# myf14.net
KiCad netlist of a schematic drawn in EAGLE
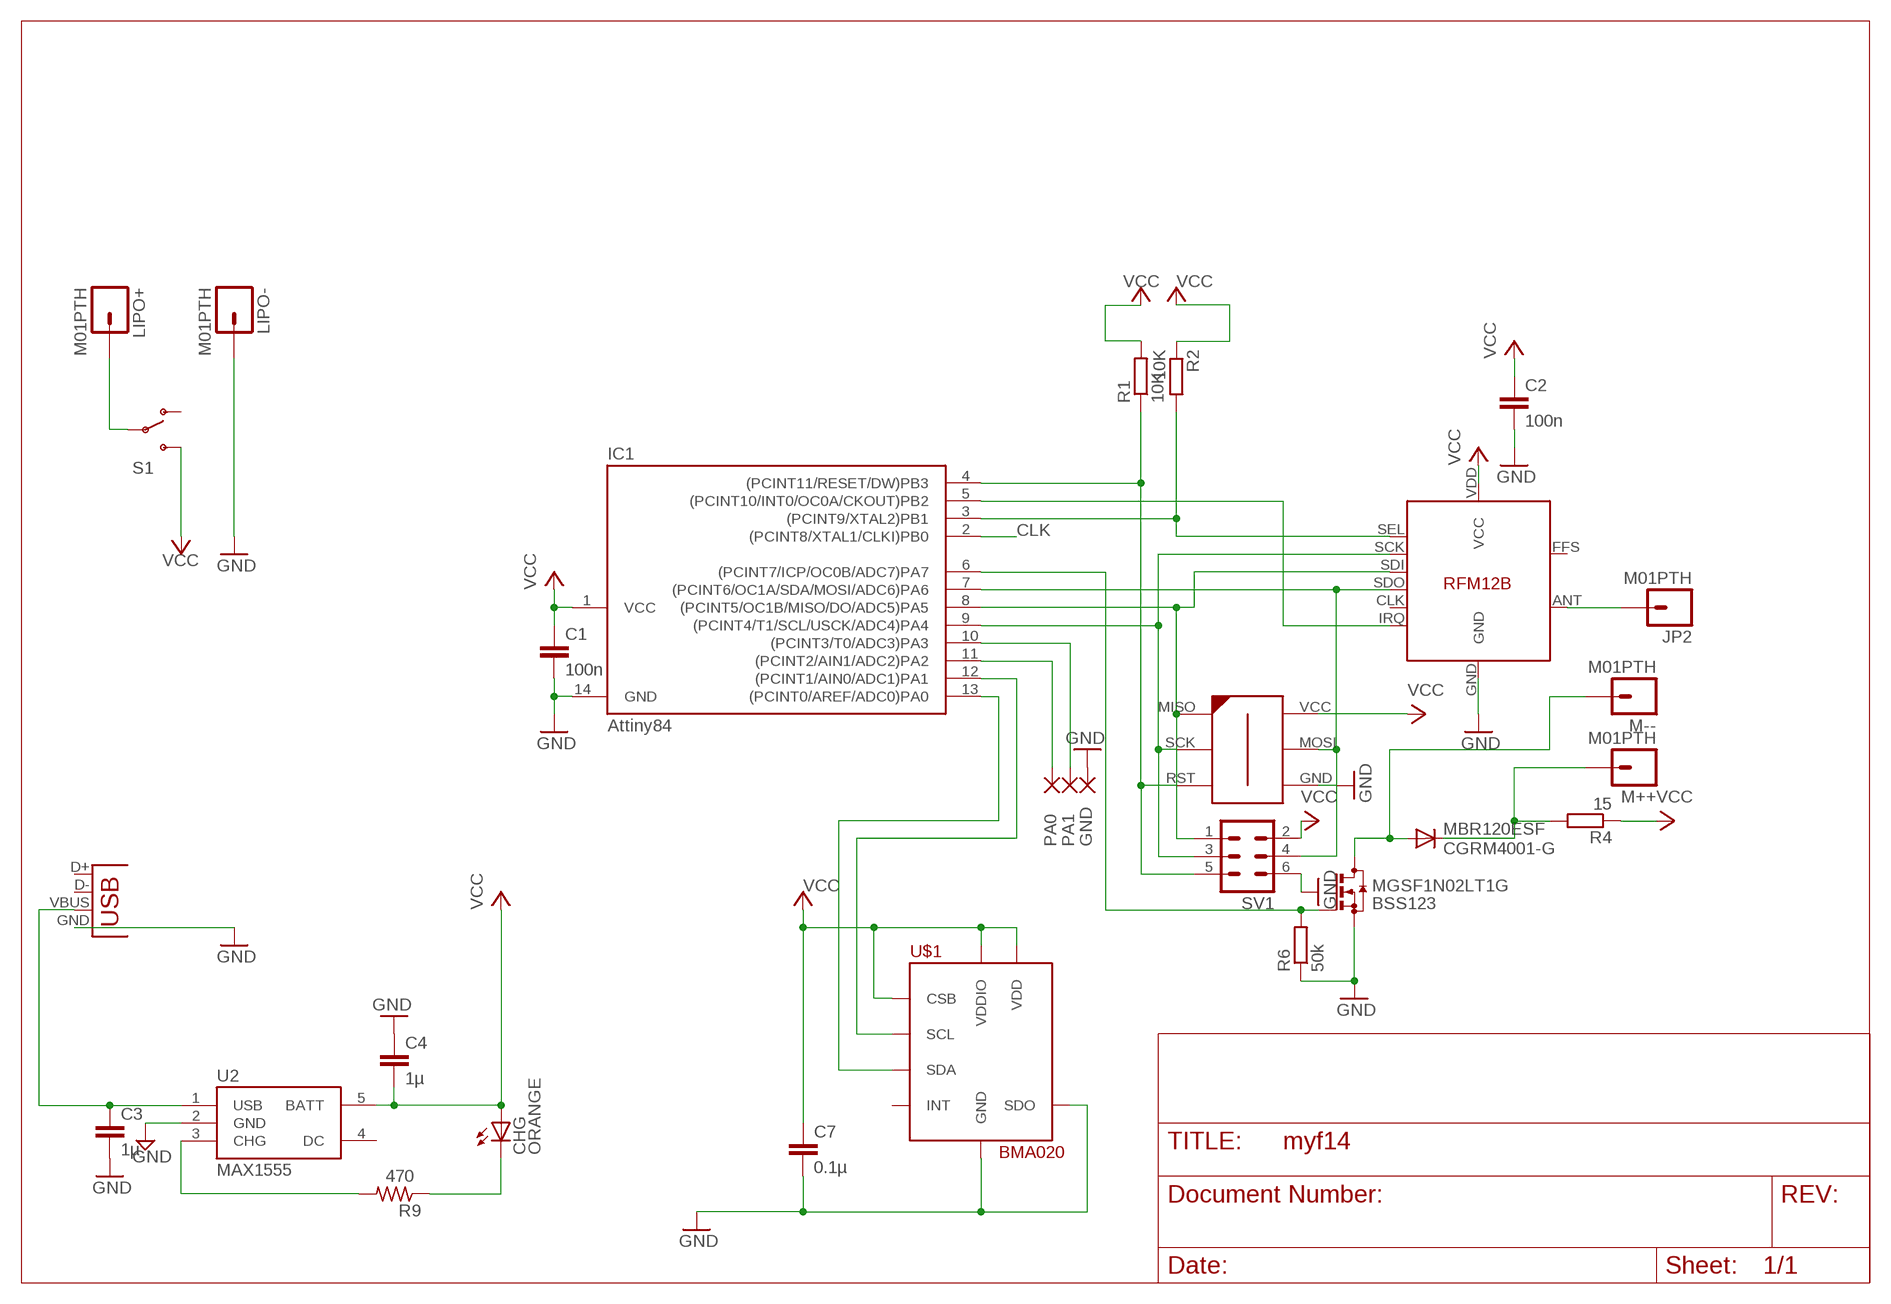
[diagram p0: schematic, sheet 1]

(export (version "E")
  (design (tool "Eeschema 10.0.6"))
  (components
    (comp (ref "C1")
      (value "100n")
      (footprint "eagle-import:C0603K")
      (libsource (lib "eagle-import") (part "C-EUC0603K"))
    )
    (comp (ref "C2")
      (value "100n")
      (footprint "eagle-import:C0603K")
      (libsource (lib "eagle-import") (part "C-EUC0603K"))
    )
    (comp (ref "C3")
      (value "1µ")
      (footprint "eagle-import:0603-CAP")
      (libsource (lib "eagle-import") (part "CAP0603-CAP"))
    )
    (comp (ref "C4")
      (value "1µ")
      (footprint "eagle-import:0603-CAP")
      (libsource (lib "eagle-import") (part "CAP0603-CAP"))
    )
    (comp (ref "C7")
      (value "0.1µ")
      (footprint "eagle-import:0603-CAP")
      (libsource (lib "eagle-import") (part "CAP0603-CAP"))
    )
    (comp (ref "CHG")
      (value "ORANGE")
      (footprint "eagle-import:LED-0603")
      (libsource (lib "eagle-import") (part "LED0603"))
    )
    (comp (ref "GND")
      (value "SMD2")
      (footprint "eagle-import:SMD1,27-2,54")
      (libsource (lib "eagle-import") (part "SMD2"))
    )
    (comp (ref "IC1")
      (value "Attiny84")
      (footprint "eagle-import:SOIC14")
      (libsource (lib "eagle-import") (part "TINY24/44/84-SSU"))
    )
    (comp (ref "JP2")
      (value "M01PTH")
      (footprint "eagle-import:1X01")
      (libsource (lib "eagle-import") (part "M01PTH"))
    )
    (comp (ref "LIPO+")
      (value "M01PTH")
      (footprint "eagle-import:1X01")
      (libsource (lib "eagle-import") (part "M01PTH"))
    )
    (comp (ref "LIPO-")
      (value "M01PTH")
      (footprint "eagle-import:1X01")
      (libsource (lib "eagle-import") (part "M01PTH"))
    )
    (comp (ref "M++")
      (value "M01PTH")
      (footprint "eagle-import:1X01")
      (libsource (lib "eagle-import") (part "M01PTH"))
    )
    (comp (ref "M--")
      (value "M01PTH")
      (footprint "eagle-import:1X01")
      (libsource (lib "eagle-import") (part "M01PTH"))
    )
    (comp (ref "MBR120ESF")
      (value "CGRM4001-G")
      (footprint "eagle-import:SOD-123_MINI-SMA")
      (libsource (lib "eagle-import") (part "CGRM400-G1"))
    )
    (comp (ref "MGSF1N02LT1G")
      (value "BSS123")
      (footprint "eagle-import:SOT23")
      (libsource (lib "eagle-import") (part "BSS123"))
    )
    (comp (ref "PA0")
      (value "SMD2")
      (footprint "eagle-import:SMD1,27-2,54")
      (libsource (lib "eagle-import") (part "SMD2"))
    )
    (comp (ref "PA1")
      (value "SMD2")
      (footprint "eagle-import:SMD1,27-2,54")
      (libsource (lib "eagle-import") (part "SMD2"))
    )
    (comp (ref "R1")
      (value "10K")
      (footprint "eagle-import:R0603")
      (libsource (lib "eagle-import") (part "R-EU_R0603"))
    )
    (comp (ref "R2")
      (value "10K")
      (footprint "eagle-import:R0603")
      (libsource (lib "eagle-import") (part "R-EU_R0603"))
    )
    (comp (ref "R4")
      (value "15")
      (footprint "eagle-import:R0603")
      (libsource (lib "eagle-import") (part "R-EU_R0603"))
    )
    (comp (ref "R6")
      (value "50k")
      (footprint "eagle-import:R0603")
      (libsource (lib "eagle-import") (part "R-EU_R0603"))
    )
    (comp (ref "R9")
      (value "470")
      (footprint "eagle-import:R0603")
      (libsource (lib "eagle-import") (part "R-US_R0603"))
    )
    (comp (ref "RFM12B")
      (value "RFM12B")
      (footprint "eagle-import:RFM12B")
      (libsource (lib "eagle-import") (part "RFM12B"))
    )
    (comp (ref "S1")
      (value "SWITCH-SPDTSMD")
      (footprint "eagle-import:AYZ0202")
      (libsource (lib "eagle-import") (part "SWITCH-SPDTSMD"))
    )
    (comp (ref "SV1")
      (value "MA03-2S")
      (footprint "eagle-import:MA03-2-0.8")
      (libsource (lib "eagle-import") (part "MA03-2S"))
    )
    (comp (ref "U$1")
      (value "BMA020")
      (footprint "eagle-import:LBA-12")
      (libsource (lib "eagle-import") (part "BMA020"))
    )
    (comp (ref "U$2")
      (value "AVR-ISP-6-EDGE")
      (footprint "eagle-import:6PAD_ISP")
      (libsource (lib "eagle-import") (part "AVR-ISP-6-EDGE"))
    )
    (comp (ref "U2")
      (value "MAX1555")
      (footprint "eagle-import:SOT23-5")
      (libsource (lib "eagle-import") (part "MAX1555"))
    )
    (comp (ref "X1")
      (value "USB-MICROB")
      (footprint "eagle-import:USB-MICROB")
      (libsource (lib "eagle-import") (part "USB-MICROB"))
    )
  )
  (nets
    (net (code "1") (name "/CLK") (class "Default")
      (node (ref "IC1") (pin "2") (pinfunction "(PCINT8/XTAL1/CLKI)PB0_2") (pintype "bidirectional"))
    )
    (net (code "2") (name "GND") (class "Default")
      (node (ref "C1") (pin "2") (pinfunction "2_2") (pintype "passive"))
      (node (ref "C2") (pin "2") (pinfunction "2_2") (pintype "passive"))
      (node (ref "C3") (pin "2") (pinfunction "2_2") (pintype "passive"))
      (node (ref "C4") (pin "1") (pinfunction "1_1") (pintype "passive"))
      (node (ref "C7") (pin "2") (pinfunction "2_2") (pintype "passive"))
      (node (ref "GND") (pin "1") (pinfunction "P_1") (pintype "passive"))
      (node (ref "IC1") (pin "14") (pinfunction "GND_14") (pintype "power_in"))
      (node (ref "LIPO-") (pin "1") (pinfunction "1_1") (pintype "passive"))
      (node (ref "MGSF1N02LT1G") (pin "2") (pinfunction "S_2") (pintype "passive"))
      (node (ref "R6") (pin "1") (pinfunction "1_1") (pintype "passive"))
      (node (ref "RFM12B") (pin "GND") (pinfunction "GND_GND") (pintype "power_in"))
      (node (ref "SV1") (pin "6") (pinfunction "6_6") (pintype "passive"))
      (node (ref "U$1") (pin "P$3") (pinfunction "GND_P$3") (pintype "power_in"))
      (node (ref "U$1") (pin "P$7") (pinfunction "SDO_P$7") (pintype "bidirectional"))
      (node (ref "U$2") (pin "GND") (pinfunction "P$4_GND") (pintype "bidirectional"))
      (node (ref "U2") (pin "2") (pinfunction "GND_2") (pintype "bidirectional"))
      (node (ref "X1") (pin "GND") (pinfunction "GND_GND") (pintype "bidirectional"))
    )
    (net (code "3") (name "Net-(CHG-PadC)") (class "Default")
      (node (ref "CHG") (pin "C") (pinfunction "C_C") (pintype "passive"))
      (node (ref "R9") (pin "1") (pinfunction "1_1") (pintype "passive"))
    )
    (net (code "4") (name "Net-(IC1-(PCINT0{slash}AREF{slash}ADC0)PA0)") (class "Default")
      (node (ref "IC1") (pin "13") (pinfunction "(PCINT0/AREF/ADC0)PA0_13") (pintype "bidirectional"))
      (node (ref "U$1") (pin "P$8") (pinfunction "SDA_P$8") (pintype "bidirectional"))
    )
    (net (code "5") (name "Net-(IC1-(PCINT1{slash}AIN0{slash}ADC1)PA1)") (class "Default")
      (node (ref "IC1") (pin "12") (pinfunction "(PCINT1/AIN0/ADC1)PA1_12") (pintype "bidirectional"))
      (node (ref "U$1") (pin "P$6") (pinfunction "SCL_P$6") (pintype "bidirectional"))
    )
    (net (code "6") (name "Net-(IC1-(PCINT2{slash}AIN1{slash}ADC2)PA2)") (class "Default")
      (node (ref "IC1") (pin "11") (pinfunction "(PCINT2/AIN1/ADC2)PA2_11") (pintype "bidirectional"))
      (node (ref "PA0") (pin "1") (pinfunction "P_1") (pintype "passive"))
    )
    (net (code "7") (name "Net-(IC1-(PCINT3{slash}T0{slash}ADC3)PA3)") (class "Default")
      (node (ref "IC1") (pin "10") (pinfunction "(PCINT3/T0/ADC3)PA3_10") (pintype "bidirectional"))
      (node (ref "PA1") (pin "1") (pinfunction "P_1") (pintype "passive"))
    )
    (net (code "8") (name "Net-(IC1-(PCINT4{slash}T1{slash}SCL{slash}USCK{slash}ADC4)PA4)") (class "Default")
      (node (ref "IC1") (pin "9") (pinfunction "(PCINT4/T1/SCL/USCK/ADC4)PA4_9") (pintype "bidirectional"))
      (node (ref "RFM12B") (pin "SCK") (pinfunction "SCK_SCK") (pintype "input"))
      (node (ref "SV1") (pin "3") (pinfunction "3_3") (pintype "passive"))
      (node (ref "U$2") (pin "SCK") (pinfunction "P$2_SCK") (pintype "bidirectional"))
    )
    (net (code "9") (name "Net-(IC1-(PCINT5{slash}OC1B{slash}MISO{slash}DO{slash}ADC5)PA5)") (class "Default")
      (node (ref "IC1") (pin "8") (pinfunction "(PCINT5/OC1B/MISO/DO/ADC5)PA5_8") (pintype "bidirectional"))
      (node (ref "RFM12B") (pin "SDI") (pinfunction "SDI_SDI") (pintype "input"))
      (node (ref "SV1") (pin "1") (pinfunction "1_1") (pintype "passive"))
      (node (ref "U$2") (pin "MISO") (pinfunction "P$1_MISO") (pintype "bidirectional"))
    )
    (net (code "10") (name "Net-(IC1-(PCINT6{slash}OC1A{slash}SDA{slash}MOSI{slash}ADC6)PA6)") (class "Default")
      (node (ref "IC1") (pin "7") (pinfunction "(PCINT6/OC1A/SDA/MOSI/ADC6)PA6_7") (pintype "bidirectional"))
      (node (ref "RFM12B") (pin "SDO") (pinfunction "SDO_SDO") (pintype "output"))
      (node (ref "SV1") (pin "4") (pinfunction "4_4") (pintype "passive"))
      (node (ref "U$2") (pin "MOSI") (pinfunction "P$5_MOSI") (pintype "bidirectional"))
    )
    (net (code "11") (name "Net-(IC1-(PCINT7{slash}ICP{slash}OC0B{slash}ADC7)PA7)") (class "Default")
      (node (ref "IC1") (pin "6") (pinfunction "(PCINT7/ICP/OC0B/ADC7)PA7_6") (pintype "bidirectional"))
      (node (ref "MGSF1N02LT1G") (pin "1") (pinfunction "G_1") (pintype "passive"))
      (node (ref "R6") (pin "2") (pinfunction "2_2") (pintype "passive"))
    )
    (net (code "12") (name "Net-(IC1-(PCINT9{slash}XTAL2)PB1)") (class "Default")
      (node (ref "IC1") (pin "3") (pinfunction "(PCINT9/XTAL2)PB1_3") (pintype "bidirectional"))
      (node (ref "R2") (pin "2") (pinfunction "2_2") (pintype "passive"))
      (node (ref "RFM12B") (pin "SEL") (pinfunction "SEL_SEL") (pintype "input"))
    )
    (net (code "13") (name "Net-(IC1-(PCINT10{slash}INT0{slash}OC0A{slash}CKOUT)PB2)") (class "Default")
      (node (ref "IC1") (pin "5") (pinfunction "(PCINT10/INT0/OC0A/CKOUT)PB2_5") (pintype "bidirectional"))
      (node (ref "RFM12B") (pin "IRQ") (pinfunction "IRQ_IRQ") (pintype "open_collector"))
    )
    (net (code "14") (name "Net-(IC1-(PCINT11{slash}RESET{slash}DW)PB3)") (class "Default")
      (node (ref "IC1") (pin "4") (pinfunction "(PCINT11/RESET/DW)PB3_4") (pintype "bidirectional"))
      (node (ref "R1") (pin "1") (pinfunction "1_1") (pintype "passive"))
      (node (ref "SV1") (pin "5") (pinfunction "5_5") (pintype "passive"))
      (node (ref "U$2") (pin "RST") (pinfunction "P$3_RST") (pintype "bidirectional"))
    )
    (net (code "15") (name "Net-(JP2-Pad1)") (class "Default")
      (node (ref "JP2") (pin "1") (pinfunction "1_1") (pintype "passive"))
      (node (ref "RFM12B") (pin "ANT") (pinfunction "ANT_ANT") (pintype "passive"))
    )
    (net (code "16") (name "Net-(M++-Pad1)") (class "Default")
      (node (ref "M++") (pin "1") (pinfunction "1_1") (pintype "passive"))
      (node (ref "MBR120ESF") (pin "C") (pinfunction "C_C") (pintype "passive"))
      (node (ref "R4") (pin "2") (pinfunction "2_2") (pintype "passive"))
    )
    (net (code "17") (name "Net-(MGSF1N02LT1G-D)") (class "Default")
      (node (ref "M--") (pin "1") (pinfunction "1_1") (pintype "passive"))
      (node (ref "MBR120ESF") (pin "A") (pinfunction "A_A") (pintype "passive"))
      (node (ref "MGSF1N02LT1G") (pin "3") (pinfunction "D_3") (pintype "passive"))
    )
    (net (code "18") (name "Net-(S1-P)") (class "Default")
      (node (ref "LIPO+") (pin "1") (pinfunction "1_1") (pintype "passive"))
      (node (ref "S1") (pin "2") (pinfunction "P_2") (pintype "passive"))
    )
    (net (code "19") (name "Net-(U2-CHG)") (class "Default")
      (node (ref "R9") (pin "2") (pinfunction "2_2") (pintype "passive"))
      (node (ref "U2") (pin "3") (pinfunction "CHG_3") (pintype "bidirectional"))
    )
    (net (code "20") (name "Net-(U2-USB)") (class "Default")
      (node (ref "C3") (pin "1") (pinfunction "1_1") (pintype "passive"))
      (node (ref "U2") (pin "1") (pinfunction "USB_1") (pintype "bidirectional"))
      (node (ref "X1") (pin "VBUS") (pinfunction "VBUS_VBUS") (pintype "bidirectional"))
    )
    (net (code "21") (name "VCC") (class "Default")
      (node (ref "C1") (pin "1") (pinfunction "1_1") (pintype "passive"))
      (node (ref "C2") (pin "1") (pinfunction "1_1") (pintype "passive"))
      (node (ref "C4") (pin "2") (pinfunction "2_2") (pintype "passive"))
      (node (ref "C7") (pin "1") (pinfunction "1_1") (pintype "passive"))
      (node (ref "CHG") (pin "A") (pinfunction "A_A") (pintype "passive"))
      (node (ref "IC1") (pin "1") (pinfunction "VCC_1") (pintype "power_in"))
      (node (ref "R1") (pin "2") (pinfunction "2_2") (pintype "passive"))
      (node (ref "R2") (pin "1") (pinfunction "1_1") (pintype "passive"))
      (node (ref "R4") (pin "1") (pinfunction "1_1") (pintype "passive"))
      (node (ref "RFM12B") (pin "VDD") (pinfunction "VCC_VDD") (pintype "power_in"))
      (node (ref "S1") (pin "3") (pinfunction "S_3") (pintype "passive"))
      (node (ref "SV1") (pin "2") (pinfunction "2_2") (pintype "passive"))
      (node (ref "U$1") (pin "P$2") (pinfunction "VDD_P$2") (pintype "power_in"))
      (node (ref "U$1") (pin "P$5") (pinfunction "CSB_P$5") (pintype "bidirectional"))
      (node (ref "U$1") (pin "P$9") (pinfunction "VDDIO_P$9") (pintype "power_in"))
      (node (ref "U$2") (pin "VCC") (pinfunction "P$6_VCC") (pintype "bidirectional"))
      (node (ref "U2") (pin "5") (pinfunction "BATT_5") (pintype "bidirectional"))
    )
    (net (code "22") (name "unconnected-(RFM12B-PadCLK)") (class "Default")
      (node (ref "RFM12B") (pin "CLK") (pinfunction "CLK_CLK") (pintype "output"))
    )
    (net (code "23") (name "unconnected-(RFM12B-PadFFS)") (class "Default")
      (node (ref "RFM12B") (pin "FFS") (pinfunction "FFS_FFS") (pintype "bidirectional"))
    )
    (net (code "24") (name "unconnected-(S1-O-Pad1)") (class "Default")
      (node (ref "S1") (pin "1") (pinfunction "O_1") (pintype "passive"))
    )
    (net (code "25") (name "unconnected-(U$1-INT-PadP$4)") (class "Default")
      (node (ref "U$1") (pin "P$4") (pinfunction "INT_P$4") (pintype "open_collector"))
    )
    (net (code "26") (name "unconnected-(U2-DC-Pad4)") (class "Default")
      (node (ref "U2") (pin "4") (pinfunction "DC_4") (pintype "bidirectional"))
    )
    (net (code "27") (name "unconnected-(X1-PadD+)") (class "Default")
      (node (ref "X1") (pin "D+") (pinfunction "D+_D+") (pintype "bidirectional"))
    )
    (net (code "28") (name "unconnected-(X1-PadD-)") (class "Default")
      (node (ref "X1") (pin "D-") (pinfunction "D-_D-") (pintype "bidirectional"))
    )
  )
)
